# d709-vs1053-synth.net
KiCad netlist of a schematic drawn in EAGLE
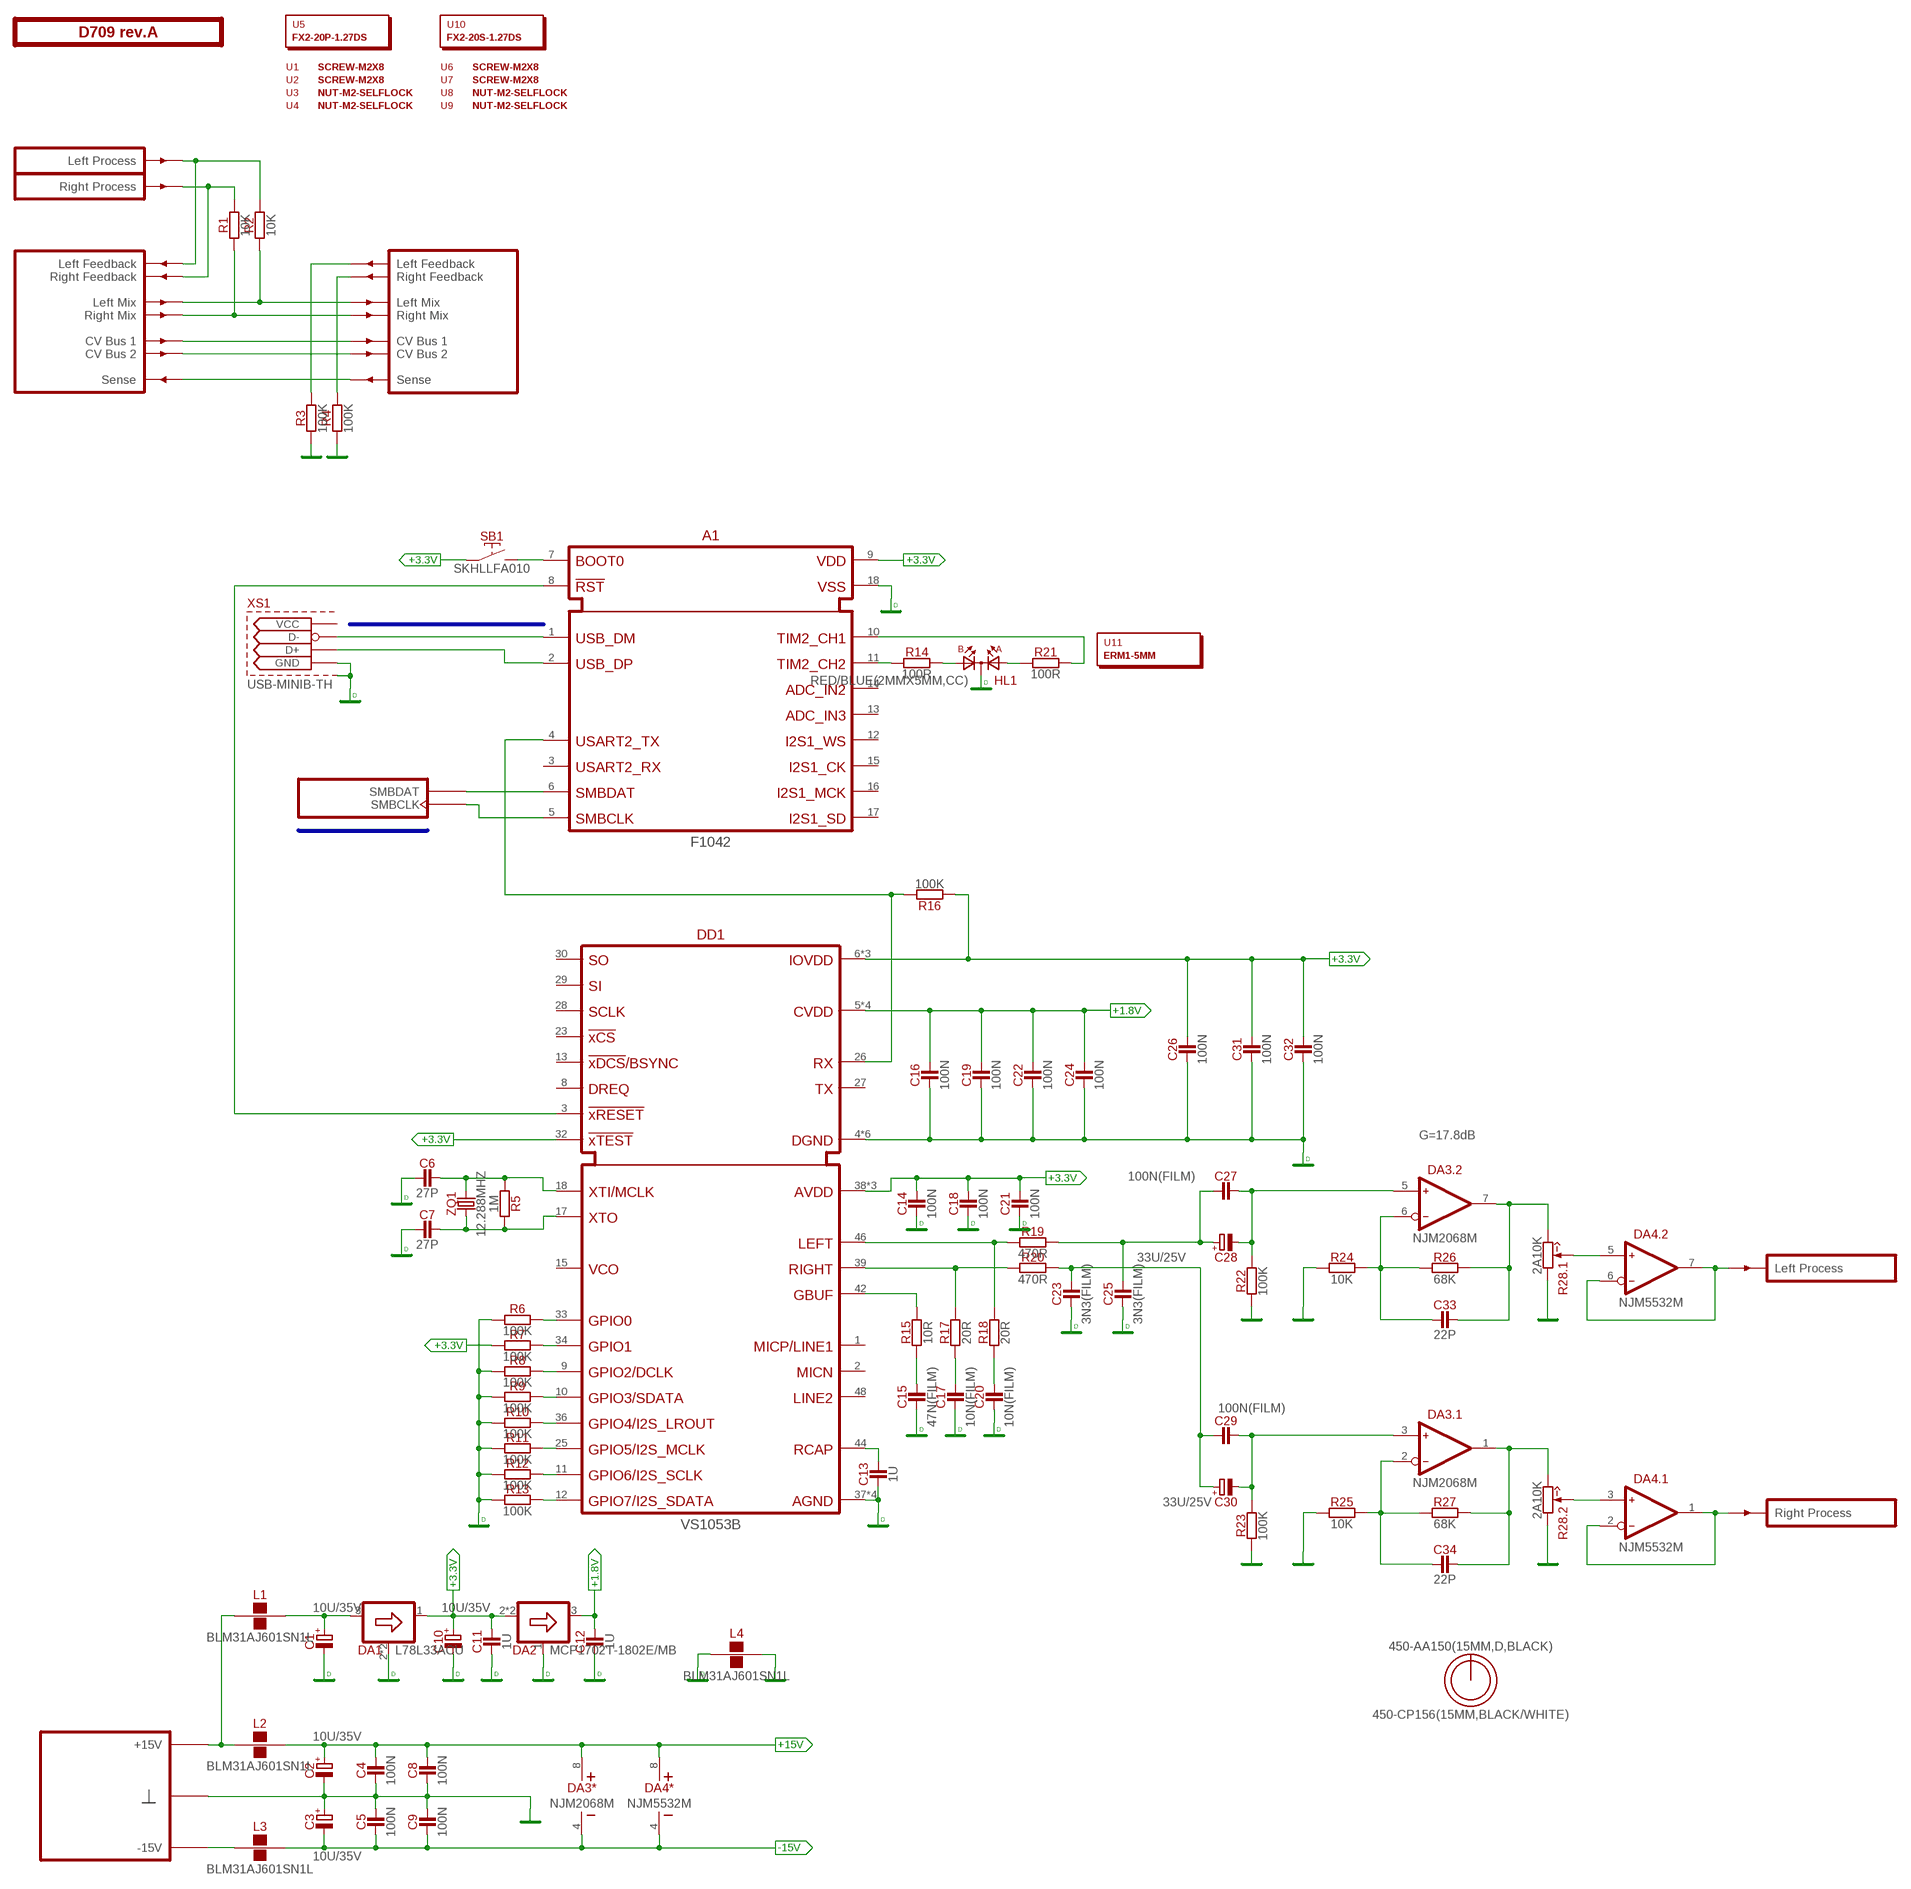
[diagram p0: schematic, sheet 1]

(export (version "E")
  (design (tool "Eeschema 10.0.6"))
  (components
    (comp (ref "A1")
      (value "F1042")
      (footprint "eagle-import:F-DIP18")
      (libsource (lib "eagle-import") (part "F1042"))
    )
    (comp (ref "C1")
      (value "10U/35V")
      (footprint "eagle-import:E2-5")
      (libsource (lib "eagle-import") (part "?10U/35V"))
    )
    (comp (ref "C2")
      (value "10U/35V")
      (footprint "eagle-import:E2-5")
      (libsource (lib "eagle-import") (part "?10U/35V"))
    )
    (comp (ref "C3")
      (value "10U/35V")
      (footprint "eagle-import:E2-5")
      (libsource (lib "eagle-import") (part "?10U/35V"))
    )
    (comp (ref "C4")
      (value "100N")
      (footprint "eagle-import:C-0805")
      (libsource (lib "eagle-import") (part "?100N"))
    )
    (comp (ref "C5")
      (value "100N")
      (footprint "eagle-import:C-0805")
      (libsource (lib "eagle-import") (part "?100N"))
    )
    (comp (ref "C6")
      (value "27P")
      (footprint "eagle-import:C-0805")
      (libsource (lib "eagle-import") (part "?27P"))
    )
    (comp (ref "C7")
      (value "27P")
      (footprint "eagle-import:C-0805")
      (libsource (lib "eagle-import") (part "?27P"))
    )
    (comp (ref "C8")
      (value "100N")
      (footprint "eagle-import:C-0805")
      (libsource (lib "eagle-import") (part "?100N"))
    )
    (comp (ref "C9")
      (value "100N")
      (footprint "eagle-import:C-0805")
      (libsource (lib "eagle-import") (part "?100N"))
    )
    (comp (ref "C10")
      (value "10U/35V")
      (footprint "eagle-import:E2-5")
      (libsource (lib "eagle-import") (part "?10U/35V"))
    )
    (comp (ref "C11")
      (value "1U")
      (footprint "eagle-import:C-0805")
      (libsource (lib "eagle-import") (part "?1U"))
    )
    (comp (ref "C12")
      (value "1U")
      (footprint "eagle-import:C-0805")
      (libsource (lib "eagle-import") (part "?1U"))
    )
    (comp (ref "C13")
      (value "1U")
      (footprint "eagle-import:C-0805")
      (libsource (lib "eagle-import") (part "?1U"))
    )
    (comp (ref "C14")
      (value "100N")
      (footprint "eagle-import:C-0805")
      (libsource (lib "eagle-import") (part "?100N"))
    )
    (comp (ref "C15")
      (value "47N(FILM)")
      (footprint "eagle-import:C050-025X075")
      (libsource (lib "eagle-import") (part "?47N(FILM)"))
    )
    (comp (ref "C16")
      (value "100N")
      (footprint "eagle-import:C-0805")
      (libsource (lib "eagle-import") (part "?100N"))
    )
    (comp (ref "C17")
      (value "10N(FILM)")
      (footprint "eagle-import:C050-025X075")
      (libsource (lib "eagle-import") (part "?10N(FILM)"))
    )
    (comp (ref "C18")
      (value "100N")
      (footprint "eagle-import:C-0805")
      (libsource (lib "eagle-import") (part "?100N"))
    )
    (comp (ref "C19")
      (value "100N")
      (footprint "eagle-import:C-0805")
      (libsource (lib "eagle-import") (part "?100N"))
    )
    (comp (ref "C20")
      (value "10N(FILM)")
      (footprint "eagle-import:C050-025X075")
      (libsource (lib "eagle-import") (part "?10N(FILM)"))
    )
    (comp (ref "C21")
      (value "100N")
      (footprint "eagle-import:C-0805")
      (libsource (lib "eagle-import") (part "?100N"))
    )
    (comp (ref "C22")
      (value "100N")
      (footprint "eagle-import:C-0805")
      (libsource (lib "eagle-import") (part "?100N"))
    )
    (comp (ref "C23")
      (value "3N3(FILM)")
      (footprint "eagle-import:C050-025X075")
      (libsource (lib "eagle-import") (part "?3N3(FILM)"))
    )
    (comp (ref "C24")
      (value "100N")
      (footprint "eagle-import:C-0805")
      (libsource (lib "eagle-import") (part "?100N"))
    )
    (comp (ref "C25")
      (value "3N3(FILM)")
      (footprint "eagle-import:C050-025X075")
      (libsource (lib "eagle-import") (part "?3N3(FILM)"))
    )
    (comp (ref "C26")
      (value "100N")
      (footprint "eagle-import:C-0805")
      (libsource (lib "eagle-import") (part "?100N"))
    )
    (comp (ref "C27")
      (value "100N(FILM)")
      (footprint "eagle-import:C050-025X075")
      (libsource (lib "eagle-import") (part "?100N(FILM)"))
    )
    (comp (ref "C28")
      (value "33U/25V")
      (footprint "eagle-import:E2,5-7")
      (libsource (lib "eagle-import") (part "?33U/25V"))
    )
    (comp (ref "C29")
      (value "100N(FILM)")
      (footprint "eagle-import:C050-025X075")
      (libsource (lib "eagle-import") (part "?100N(FILM)"))
    )
    (comp (ref "C30")
      (value "33U/25V")
      (footprint "eagle-import:E2,5-7")
      (libsource (lib "eagle-import") (part "?33U/25V"))
    )
    (comp (ref "C31")
      (value "100N")
      (footprint "eagle-import:C-0805")
      (libsource (lib "eagle-import") (part "?100N"))
    )
    (comp (ref "C32")
      (value "100N")
      (footprint "eagle-import:C-0805")
      (libsource (lib "eagle-import") (part "?100N"))
    )
    (comp (ref "C33")
      (value "22P")
      (footprint "eagle-import:C-0805")
      (libsource (lib "eagle-import") (part "?22P"))
    )
    (comp (ref "C34")
      (value "22P")
      (footprint "eagle-import:C-0805")
      (libsource (lib "eagle-import") (part "?22P"))
    )
    (comp (ref "DA1")
      (value "L78L33ACU")
      (footprint "eagle-import:SOT89")
      (libsource (lib "eagle-import") (part "?L78L33ACU"))
    )
    (comp (ref "DA2")
      (value "MCP1702T-1802E/MB")
      (footprint "eagle-import:SOT89")
      (libsource (lib "eagle-import") (part "?MCP1702T-1802E/MB"))
    )
    (comp (ref "DA3")
      (value "NJM2068M")
      (footprint "eagle-import:SO-8")
      (libsource (lib "eagle-import") (part "NJM2068M"))
    )
    (comp (ref "DA4")
      (value "NJM5532M")
      (footprint "eagle-import:SO-8")
      (libsource (lib "eagle-import") (part "NJM5532M"))
    )
    (comp (ref "DD1")
      (value "VS1053B")
      (footprint "eagle-import:LQFP48-7X7")
      (libsource (lib "eagle-import") (part "VS1053B"))
    )
    (comp (ref "HL1")
      (value "RED/BLUE(2MMX5MM,CC)")
      (footprint "eagle-import:LED2X5-3PIN")
      (libsource (lib "eagle-import") (part "?(2MMX5MM,CC)RED/BLUE"))
    )
    (comp (ref "L1")
      (value "BLM31AJ601SN1L")
      (footprint "eagle-import:1206")
      (libsource (lib "eagle-import") (part "BLM31AJ601SN1L"))
    )
    (comp (ref "L2")
      (value "BLM31AJ601SN1L")
      (footprint "eagle-import:1206")
      (libsource (lib "eagle-import") (part "BLM31AJ601SN1L"))
    )
    (comp (ref "L3")
      (value "BLM31AJ601SN1L")
      (footprint "eagle-import:1206")
      (libsource (lib "eagle-import") (part "BLM31AJ601SN1L"))
    )
    (comp (ref "L4")
      (value "BLM31AJ601SN1L")
      (footprint "eagle-import:1206")
      (libsource (lib "eagle-import") (part "BLM31AJ601SN1L"))
    )
    (comp (ref "O1")
      (value "450-AA150(15MM,D,BLACK)")
      (footprint "eagle-import:EMPTY")
      (libsource (lib "eagle-import") (part "450-AA?150(15MM,D,BLACK)"))
    )
    (comp (ref "O2")
      (value "450-CP156(15MM,BLACK/WHITE)")
      (footprint "eagle-import:EMPTY")
      (libsource (lib "eagle-import") (part "450-C?P156(15MM,BLACK/WHITE)"))
    )
    (comp (ref "PCB1")
      (value "D709 rev.A")
      (footprint "eagle-import:ST2-BOARD-50")
      (libsource (lib "eagle-import") (part "ST2-BOARD-?50"))
    )
    (comp (ref "R1")
      (value "10K")
      (footprint "eagle-import:R-0805")
      (libsource (lib "eagle-import") (part "?10K"))
    )
    (comp (ref "R2")
      (value "10K")
      (footprint "eagle-import:R-0805")
      (libsource (lib "eagle-import") (part "?10K"))
    )
    (comp (ref "R3")
      (value "100K")
      (footprint "eagle-import:R-0805")
      (libsource (lib "eagle-import") (part "?100K"))
    )
    (comp (ref "R4")
      (value "100K")
      (footprint "eagle-import:R-0805")
      (libsource (lib "eagle-import") (part "?100K"))
    )
    (comp (ref "R5")
      (value "1M")
      (footprint "eagle-import:R-0805")
      (libsource (lib "eagle-import") (part "?1M"))
    )
    (comp (ref "R6")
      (value "100K")
      (footprint "eagle-import:R-0805")
      (libsource (lib "eagle-import") (part "?100K"))
    )
    (comp (ref "R7")
      (value "100K")
      (footprint "eagle-import:R-0805")
      (libsource (lib "eagle-import") (part "?100K"))
    )
    (comp (ref "R8")
      (value "100K")
      (footprint "eagle-import:R-0805")
      (libsource (lib "eagle-import") (part "?100K"))
    )
    (comp (ref "R9")
      (value "100K")
      (footprint "eagle-import:R-0805")
      (libsource (lib "eagle-import") (part "?100K"))
    )
    (comp (ref "R10")
      (value "100K")
      (footprint "eagle-import:R-0805")
      (libsource (lib "eagle-import") (part "?100K"))
    )
    (comp (ref "R11")
      (value "100K")
      (footprint "eagle-import:R-0805")
      (libsource (lib "eagle-import") (part "?100K"))
    )
    (comp (ref "R12")
      (value "100K")
      (footprint "eagle-import:R-0805")
      (libsource (lib "eagle-import") (part "?100K"))
    )
    (comp (ref "R13")
      (value "100K")
      (footprint "eagle-import:R-0805")
      (libsource (lib "eagle-import") (part "?100K"))
    )
    (comp (ref "R14")
      (value "100R")
      (footprint "eagle-import:R-0805")
      (libsource (lib "eagle-import") (part "?100R"))
    )
    (comp (ref "R15")
      (value "10R")
      (footprint "eagle-import:R-0805")
      (libsource (lib "eagle-import") (part "?10R"))
    )
    (comp (ref "R16")
      (value "100K")
      (footprint "eagle-import:R-0805")
      (libsource (lib "eagle-import") (part "?100K"))
    )
    (comp (ref "R17")
      (value "20R")
      (footprint "eagle-import:R-0805")
      (libsource (lib "eagle-import") (part "?20R"))
    )
    (comp (ref "R18")
      (value "20R")
      (footprint "eagle-import:R-0805")
      (libsource (lib "eagle-import") (part "?20R"))
    )
    (comp (ref "R19")
      (value "470R")
      (footprint "eagle-import:R-0805")
      (libsource (lib "eagle-import") (part "?470R"))
    )
    (comp (ref "R20")
      (value "470R")
      (footprint "eagle-import:R-0805")
      (libsource (lib "eagle-import") (part "?470R"))
    )
    (comp (ref "R21")
      (value "100R")
      (footprint "eagle-import:R-0805")
      (libsource (lib "eagle-import") (part "?100R"))
    )
    (comp (ref "R22")
      (value "100K")
      (footprint "eagle-import:R-0805")
      (libsource (lib "eagle-import") (part "?100K"))
    )
    (comp (ref "R23")
      (value "100K")
      (footprint "eagle-import:R-0805")
      (libsource (lib "eagle-import") (part "?100K"))
    )
    (comp (ref "R24")
      (value "10K")
      (footprint "eagle-import:R-0805")
      (libsource (lib "eagle-import") (part "?10K"))
    )
    (comp (ref "R25")
      (value "10K")
      (footprint "eagle-import:R-0805")
      (libsource (lib "eagle-import") (part "?10K"))
    )
    (comp (ref "R26")
      (value "68K")
      (footprint "eagle-import:R-0805")
      (libsource (lib "eagle-import") (part "?68K"))
    )
    (comp (ref "R27")
      (value "68K")
      (footprint "eagle-import:R-0805")
      (libsource (lib "eagle-import") (part "?68K"))
    )
    (comp (ref "R28")
      (value "2A10K")
      (footprint "eagle-import:RV11-DUAL")
      (libsource (lib "eagle-import") (part "2?A10K"))
    )
    (comp (ref "SB1")
      (value "SKHLLFA010")
      (footprint "eagle-import:SKHLLFA010")
      (libsource (lib "eagle-import") (part "SKHLLFA010"))
    )
    (comp (ref "U1")
      (value "SCREW-M2X8")
      (footprint "eagle-import:EMPTY")
      (libsource (lib "eagle-import") (part "?SCREW-M2X8"))
    )
    (comp (ref "U2")
      (value "SCREW-M2X8")
      (footprint "eagle-import:EMPTY")
      (libsource (lib "eagle-import") (part "?SCREW-M2X8"))
    )
    (comp (ref "U3")
      (value "NUT-M2-SELFLOCK")
      (footprint "eagle-import:EMPTY")
      (libsource (lib "eagle-import") (part "?NUT-M2-SELFLOCK"))
    )
    (comp (ref "U4")
      (value "NUT-M2-SELFLOCK")
      (footprint "eagle-import:EMPTY")
      (libsource (lib "eagle-import") (part "?NUT-M2-SELFLOCK"))
    )
    (comp (ref "U5")
      (value "FX2-20P-1.27DS")
      (footprint "eagle-import:EMPTY")
      (libsource (lib "eagle-import") (part "?FX2-20P-1.27DS"))
    )
    (comp (ref "U6")
      (value "SCREW-M2X8")
      (footprint "eagle-import:EMPTY")
      (libsource (lib "eagle-import") (part "?SCREW-M2X8"))
    )
    (comp (ref "U7")
      (value "SCREW-M2X8")
      (footprint "eagle-import:EMPTY")
      (libsource (lib "eagle-import") (part "?SCREW-M2X8"))
    )
    (comp (ref "U8")
      (value "NUT-M2-SELFLOCK")
      (footprint "eagle-import:EMPTY")
      (libsource (lib "eagle-import") (part "?NUT-M2-SELFLOCK"))
    )
    (comp (ref "U9")
      (value "NUT-M2-SELFLOCK")
      (footprint "eagle-import:EMPTY")
      (libsource (lib "eagle-import") (part "?NUT-M2-SELFLOCK"))
    )
    (comp (ref "U10")
      (value "FX2-20S-1.27DS")
      (footprint "eagle-import:EMPTY")
      (libsource (lib "eagle-import") (part "?FX2-20S-1.27DS"))
    )
    (comp (ref "U11")
      (value "ERM1-5MM")
      (footprint "eagle-import:EMPTY")
      (libsource (lib "eagle-import") (part "?ERM1-5MM"))
    )
    (comp (ref "XS1")
      (value "USB-MINIB-TH")
      (footprint "eagle-import:USB-MB-H")
      (libsource (lib "eagle-import") (part "USB-MINIB-TH"))
    )
    (comp (ref "ZQ1")
      (value "12.288MHZ")
      (footprint "eagle-import:3225")
      (libsource (lib "eagle-import") (part "?12.288MHZ"))
    )
  )
  (nets
    (net (code "1") (name "+1.8V") (class "Default")
      (node (ref "C12") (pin "2") (pinfunction "2_2") (pintype "passive"))
      (node (ref "C16") (pin "2") (pinfunction "2_2") (pintype "passive"))
      (node (ref "C19") (pin "2") (pinfunction "2_2") (pintype "passive"))
      (node (ref "C22") (pin "2") (pinfunction "2_2") (pintype "passive"))
      (node (ref "C24") (pin "2") (pinfunction "2_2") (pintype "passive"))
      (node (ref "DA2") (pin "3") (pinfunction "OUT_3") (pintype "power_in"))
      (node (ref "DD1") (pin "24") (pinfunction "CVDD_24") (pintype "input"))
      (node (ref "DD1") (pin "31") (pinfunction "CVDD_31") (pintype "input"))
      (node (ref "DD1") (pin "5") (pinfunction "CVDD_5") (pintype "input"))
      (node (ref "DD1") (pin "7") (pinfunction "CVDD_7") (pintype "input"))
    )
    (net (code "2") (name "+3.3V") (class "Default")
      (node (ref "A1") (pin "9") (pinfunction "VDD_9") (pintype "input"))
      (node (ref "C10") (pin "+") (pinfunction "+_+") (pintype "passive"))
      (node (ref "C11") (pin "2") (pinfunction "2_2") (pintype "passive"))
      (node (ref "C14") (pin "2") (pinfunction "2_2") (pintype "passive"))
      (node (ref "C18") (pin "2") (pinfunction "2_2") (pintype "passive"))
      (node (ref "C21") (pin "2") (pinfunction "2_2") (pintype "passive"))
      (node (ref "C26") (pin "2") (pinfunction "2_2") (pintype "passive"))
      (node (ref "C31") (pin "2") (pinfunction "2_2") (pintype "passive"))
      (node (ref "C32") (pin "2") (pinfunction "2_2") (pintype "passive"))
      (node (ref "DA1") (pin "1") (pinfunction "OUT_1") (pintype "power_in"))
      (node (ref "DA2") (pin "2") (pinfunction "IN_2") (pintype "power_in"))
      (node (ref "DA2") (pin "2@1") (pinfunction "IN_2@1") (pintype "power_in"))
      (node (ref "DD1") (pin "14") (pinfunction "IOVDD_14") (pintype "input"))
      (node (ref "DD1") (pin "19") (pinfunction "IOVDD_19") (pintype "input"))
      (node (ref "DD1") (pin "32") (pinfunction "~{XTEST}_32") (pintype "input"))
      (node (ref "DD1") (pin "38") (pinfunction "AVDD_38") (pintype "input"))
      (node (ref "DD1") (pin "43") (pinfunction "AVDD_43") (pintype "input"))
      (node (ref "DD1") (pin "45") (pinfunction "AVDD_45") (pintype "input"))
      (node (ref "DD1") (pin "6") (pinfunction "IOVDD_6") (pintype "input"))
      (node (ref "R16") (pin "1") (pinfunction "1_1") (pintype "passive"))
      (node (ref "R7") (pin "1") (pinfunction "1_1") (pintype "passive"))
      (node (ref "SB1") (pin "1") (pinfunction "1_1") (pintype "passive"))
    )
    (net (code "3") (name "+15V") (class "Default")
      (node (ref "C2") (pin "+") (pinfunction "+_+") (pintype "passive"))
      (node (ref "C4") (pin "2") (pinfunction "2_2") (pintype "passive"))
      (node (ref "C8") (pin "2") (pinfunction "2_2") (pintype "passive"))
      (node (ref "DA3") (pin "8") (pinfunction "V+_8") (pintype "power_in"))
      (node (ref "DA4") (pin "8") (pinfunction "V+_8") (pintype "power_in"))
      (node (ref "L2") (pin "2") (pinfunction "2_2") (pintype "passive"))
    )
    (net (code "4") (name "-15V") (class "Default")
      (node (ref "C3") (pin "-") (pinfunction "-_-") (pintype "passive"))
      (node (ref "C5") (pin "1") (pinfunction "1_1") (pintype "passive"))
      (node (ref "C9") (pin "1") (pinfunction "1_1") (pintype "passive"))
      (node (ref "DA3") (pin "4") (pinfunction "V-_4") (pintype "power_in"))
      (node (ref "DA4") (pin "4") (pinfunction "V-_4") (pintype "power_in"))
      (node (ref "L3") (pin "2") (pinfunction "2_2") (pintype "passive"))
    )
    (net (code "5") (name "DGND") (class "Default")
      (node (ref "A1") (pin "18") (pinfunction "VSS_18") (pintype "input"))
      (node (ref "C1") (pin "-") (pinfunction "-_-") (pintype "passive"))
      (node (ref "C10") (pin "-") (pinfunction "-_-") (pintype "passive"))
      (node (ref "C11") (pin "1") (pinfunction "1_1") (pintype "passive"))
      (node (ref "C12") (pin "1") (pinfunction "1_1") (pintype "passive"))
      (node (ref "C13") (pin "1") (pinfunction "1_1") (pintype "passive"))
      (node (ref "C14") (pin "1") (pinfunction "1_1") (pintype "passive"))
      (node (ref "C15") (pin "1") (pinfunction "1_1") (pintype "passive"))
      (node (ref "C16") (pin "1") (pinfunction "1_1") (pintype "passive"))
      (node (ref "C17") (pin "1") (pinfunction "1_1") (pintype "passive"))
      (node (ref "C18") (pin "1") (pinfunction "1_1") (pintype "passive"))
      (node (ref "C19") (pin "1") (pinfunction "1_1") (pintype "passive"))
      (node (ref "C20") (pin "1") (pinfunction "1_1") (pintype "passive"))
      (node (ref "C21") (pin "1") (pinfunction "1_1") (pintype "passive"))
      (node (ref "C22") (pin "1") (pinfunction "1_1") (pintype "passive"))
      (node (ref "C23") (pin "1") (pinfunction "1_1") (pintype "passive"))
      (node (ref "C24") (pin "1") (pinfunction "1_1") (pintype "passive"))
      (node (ref "C25") (pin "1") (pinfunction "1_1") (pintype "passive"))
      (node (ref "C26") (pin "1") (pinfunction "1_1") (pintype "passive"))
      (node (ref "C31") (pin "1") (pinfunction "1_1") (pintype "passive"))
      (node (ref "C32") (pin "1") (pinfunction "1_1") (pintype "passive"))
      (node (ref "C6") (pin "1") (pinfunction "1_1") (pintype "passive"))
      (node (ref "C7") (pin "1") (pinfunction "1_1") (pintype "passive"))
      (node (ref "DA1") (pin "2") (pinfunction "GND_2") (pintype "power_in"))
      (node (ref "DA1") (pin "2@1") (pinfunction "GND_2@1") (pintype "power_in"))
      (node (ref "DA2") (pin "1") (pinfunction "GND_1") (pintype "power_in"))
      (node (ref "DD1") (pin "16") (pinfunction "DGND_16") (pintype "input"))
      (node (ref "DD1") (pin "20") (pinfunction "DGND_20") (pintype "input"))
      (node (ref "DD1") (pin "21") (pinfunction "DGND_21") (pintype "input"))
      (node (ref "DD1") (pin "22") (pinfunction "DGND_22") (pintype "input"))
      (node (ref "DD1") (pin "35") (pinfunction "DGND_35") (pintype "input"))
      (node (ref "DD1") (pin "37") (pinfunction "AGND_37") (pintype "input"))
      (node (ref "DD1") (pin "4") (pinfunction "DGND_4") (pintype "input"))
      (node (ref "DD1") (pin "40") (pinfunction "AGND_40") (pintype "input"))
      (node (ref "DD1") (pin "41") (pinfunction "AGND_41") (pintype "input"))
      (node (ref "DD1") (pin "47") (pinfunction "AGND_47") (pintype "input"))
      (node (ref "HL1") (pin "K") (pinfunction "K_K") (pintype "passive"))
      (node (ref "L4") (pin "1") (pinfunction "1_1") (pintype "passive"))
      (node (ref "R10") (pin "1") (pinfunction "1_1") (pintype "passive"))
      (node (ref "R11") (pin "1") (pinfunction "1_1") (pintype "passive"))
      (node (ref "R12") (pin "1") (pinfunction "1_1") (pintype "passive"))
      (node (ref "R13") (pin "1") (pinfunction "1_1") (pintype "passive"))
      (node (ref "R6") (pin "1") (pinfunction "1_1") (pintype "passive"))
      (node (ref "R8") (pin "1") (pinfunction "1_1") (pintype "passive"))
      (node (ref "R9") (pin "1") (pinfunction "1_1") (pintype "passive"))
      (node (ref "XS1") (pin "GND") (pinfunction "GND_GND") (pintype "passive"))
      (node (ref "XS1") (pin "P$1") (pinfunction "S1_P$1") (pintype "passive"))
      (node (ref "XS1") (pin "P$2") (pinfunction "S1_P$2") (pintype "passive"))
      (node (ref "XS1") (pin "P$6") (pinfunction "S1_P$6") (pintype "passive"))
      (node (ref "XS1") (pin "P$7") (pinfunction "S1_P$7") (pintype "passive"))
    )
    (net (code "6") (name "GND") (class "Default")
      (node (ref "C2") (pin "-") (pinfunction "-_-") (pintype "passive"))
      (node (ref "C3") (pin "+") (pinfunction "+_+") (pintype "passive"))
      (node (ref "C4") (pin "1") (pinfunction "1_1") (pintype "passive"))
      (node (ref "C5") (pin "2") (pinfunction "2_2") (pintype "passive"))
      (node (ref "C8") (pin "1") (pinfunction "1_1") (pintype "passive"))
      (node (ref "C9") (pin "2") (pinfunction "2_2") (pintype "passive"))
      (node (ref "L4") (pin "2") (pinfunction "2_2") (pintype "passive"))
      (node (ref "PCB1") (pin "B4") (pinfunction "GND_B4") (pintype "bidirectional"))
      (node (ref "PCB1") (pin "B4'") (pinfunction "GND_B4'") (pintype "bidirectional"))
      (node (ref "PCB1") (pin "B5") (pinfunction "GND_B5") (pintype "bidirectional"))
      (node (ref "PCB1") (pin "B5'") (pinfunction "GND_B5'") (pintype "bidirectional"))
      (node (ref "PCB1") (pin "B6") (pinfunction "GND_B6") (pintype "bidirectional"))
      (node (ref "PCB1") (pin "B6'") (pinfunction "GND_B6'") (pintype "bidirectional"))
      (node (ref "PCB1") (pin "B7") (pinfunction "GND_B7") (pintype "bidirectional"))
      (node (ref "PCB1") (pin "B7'") (pinfunction "GND_B7'") (pintype "bidirectional"))
      (node (ref "PCB1") (pin "B8") (pinfunction "GND_B8") (pintype "bidirectional"))
      (node (ref "PCB1") (pin "B8'") (pinfunction "GND_B8'") (pintype "bidirectional"))
      (node (ref "R22") (pin "1") (pinfunction "1_1") (pintype "passive"))
      (node (ref "R23") (pin "1") (pinfunction "1_1") (pintype "passive"))
      (node (ref "R24") (pin "1") (pinfunction "1_1") (pintype "passive"))
      (node (ref "R25") (pin "1") (pinfunction "1_1") (pintype "passive"))
      (node (ref "R28") (pin "1") (pinfunction "CCW_1") (pintype "passive"))
      (node (ref "R28") (pin "1'") (pinfunction "CCW_1'") (pintype "passive"))
      (node (ref "R3") (pin "1") (pinfunction "1_1") (pintype "passive"))
      (node (ref "R4") (pin "1") (pinfunction "1_1") (pintype "passive"))
    )
    (net (code "7") (name "Net-(A1-BOOT0)") (class "Default")
      (node (ref "A1") (pin "7") (pinfunction "BOOT0_7") (pintype "input"))
      (node (ref "SB1") (pin "2") (pinfunction "2_2") (pintype "passive"))
    )
    (net (code "8") (name "Net-(A1-SBMDAT)") (class "Default")
      (node (ref "A1") (pin "6") (pinfunction "SBMDAT_6") (pintype "input"))
      (node (ref "PCB1") (pin "ASMBDAT") (pinfunction "SMBDAT_ASMBDAT") (pintype "bidirectional"))
      (node (ref "PCB1") (pin "ASMBDAT'") (pinfunction "SMBDAT_ASMBDAT'") (pintype "bidirectional"))
    )
    (net (code "9") (name "Net-(A1-SMBCLK)") (class "Default")
      (node (ref "A1") (pin "5") (pinfunction "SMBCLK_5") (pintype "input"))
      (node (ref "PCB1") (pin "ASMBCLK") (pinfunction "SMBCLK_ASMBCLK") (pintype "bidirectional"))
      (node (ref "PCB1") (pin "ASMBCLK'") (pinfunction "SMBCLK_ASMBCLK'") (pintype "bidirectional"))
    )
    (net (code "10") (name "Net-(A1-TIM2_CH1)") (class "Default")
      (node (ref "A1") (pin "10") (pinfunction "TIM2_CH1_10") (pintype "input"))
      (node (ref "R21") (pin "2") (pinfunction "2_2") (pintype "passive"))
    )
    (net (code "11") (name "Net-(A1-TIM2_CH2)") (class "Default")
      (node (ref "A1") (pin "11") (pinfunction "TIM2_CH2_11") (pintype "input"))
      (node (ref "R14") (pin "1") (pinfunction "1_1") (pintype "passive"))
    )
    (net (code "12") (name "Net-(A1-USART2_TX)") (class "Default")
      (node (ref "A1") (pin "4") (pinfunction "USART2_TX_4") (pintype "input"))
      (node (ref "DD1") (pin "26") (pinfunction "RX_26") (pintype "input"))
      (node (ref "R16") (pin "2") (pinfunction "2_2") (pintype "passive"))
    )
    (net (code "13") (name "Net-(A1-USB_DM)") (class "Default")
      (node (ref "A1") (pin "1") (pinfunction "USB_DM_1") (pintype "input"))
      (node (ref "XS1") (pin "D-") (pinfunction "D-_D-") (pintype "bidirectional"))
    )
    (net (code "14") (name "Net-(A1-USB_DP)") (class "Default")
      (node (ref "A1") (pin "2") (pinfunction "USB_DP_2") (pintype "input"))
      (node (ref "XS1") (pin "D+") (pinfunction "D+_D+") (pintype "bidirectional"))
    )
    (net (code "15") (name "Net-(A1-~{RST})") (class "Default")
      (node (ref "A1") (pin "8") (pinfunction "~{RST}_8") (pintype "input"))
      (node (ref "DD1") (pin "3") (pinfunction "~{XRESET}_3") (pintype "input"))
    )
    (net (code "16") (name "Net-(C15-Pad2)") (class "Default")
      (node (ref "C15") (pin "2") (pinfunction "2_2") (pintype "passive"))
      (node (ref "R15") (pin "1") (pinfunction "1_1") (pintype "passive"))
    )
    (net (code "17") (name "Net-(C17-Pad2)") (class "Default")
      (node (ref "C17") (pin "2") (pinfunction "2_2") (pintype "passive"))
      (node (ref "R17") (pin "1") (pinfunction "1_1") (pintype "passive"))
    )
    (net (code "18") (name "Net-(C20-Pad2)") (class "Default")
      (node (ref "C20") (pin "2") (pinfunction "2_2") (pintype "passive"))
      (node (ref "R18") (pin "1") (pinfunction "1_1") (pintype "passive"))
    )
    (net (code "19") (name "Net-(C23-Pad2)") (class "Default")
      (node (ref "C23") (pin "2") (pinfunction "2_2") (pintype "passive"))
      (node (ref "C29") (pin "1") (pinfunction "1_1") (pintype "passive"))
      (node (ref "C30") (pin "+") (pinfunction "+_+") (pintype "passive"))
      (node (ref "R20") (pin "2") (pinfunction "2_2") (pintype "passive"))
    )
    (net (code "20") (name "Net-(C25-Pad2)") (class "Default")
      (node (ref "C25") (pin "2") (pinfunction "2_2") (pintype "passive"))
      (node (ref "C27") (pin "1") (pinfunction "1_1") (pintype "passive"))
      (node (ref "C28") (pin "+") (pinfunction "+_+") (pintype "passive"))
      (node (ref "R19") (pin "2") (pinfunction "2_2") (pintype "passive"))
    )
    (net (code "21") (name "Net-(DA1-IN)") (class "Default")
      (node (ref "C1") (pin "+") (pinfunction "+_+") (pintype "passive"))
      (node (ref "DA1") (pin "3") (pinfunction "IN_3") (pintype "power_in"))
      (node (ref "L1") (pin "2") (pinfunction "2_2") (pintype "passive"))
    )
    (net (code "22") (name "Net-(DA3B-IN+)") (class "Default")
      (node (ref "C29") (pin "2") (pinfunction "2_2") (pintype "passive"))
      (node (ref "C30") (pin "-") (pinfunction "-_-") (pintype "passive"))
      (node (ref "DA3") (pin "3") (pinfunction "IN+_3") (pintype "input"))
      (node (ref "R23") (pin "2") (pinfunction "2_2") (pintype "passive"))
    )
    (net (code "23") (name "Net-(DA3B-IN-)") (class "Default")
      (node (ref "C34") (pin "1") (pinfunction "1_1") (pintype "passive"))
      (node (ref "DA3") (pin "2") (pinfunction "IN-_2") (pintype "input"))
      (node (ref "R25") (pin "2") (pinfunction "2_2") (pintype "passive"))
      (node (ref "R27") (pin "1") (pinfunction "1_1") (pintype "passive"))
    )
    (net (code "24") (name "Net-(DA3B-OUT)") (class "Default")
      (node (ref "C34") (pin "2") (pinfunction "2_2") (pintype "passive"))
      (node (ref "DA3") (pin "1") (pinfunction "OUT_1") (pintype "output"))
      (node (ref "R27") (pin "2") (pinfunction "2_2") (pintype "passive"))
      (node (ref "R28") (pin "3'") (pinfunction "CW_3'") (pintype "passive"))
    )
    (net (code "25") (name "Net-(DA3C-IN+)") (class "Default")
      (node (ref "C27") (pin "2") (pinfunction "2_2") (pintype "passive"))
      (node (ref "C28") (pin "-") (pinfunction "-_-") (pintype "passive"))
      (node (ref "DA3") (pin "5") (pinfunction "IN+_5") (pintype "input"))
      (node (ref "R22") (pin "2") (pinfunction "2_2") (pintype "passive"))
    )
    (net (code "26") (name "Net-(DA3C-IN-)") (class "Default")
      (node (ref "C33") (pin "1") (pinfunction "1_1") (pintype "passive"))
      (node (ref "DA3") (pin "6") (pinfunction "IN-_6") (pintype "input"))
      (node (ref "R24") (pin "2") (pinfunction "2_2") (pintype "passive"))
      (node (ref "R26") (pin "1") (pinfunction "1_1") (pintype "passive"))
    )
    (net (code "27") (name "Net-(DA3C-OUT)") (class "Default")
      (node (ref "C33") (pin "2") (pinfunction "2_2") (pintype "passive"))
      (node (ref "DA3") (pin "7") (pinfunction "OUT_7") (pintype "output"))
      (node (ref "R26") (pin "2") (pinfunction "2_2") (pintype "passive"))
      (node (ref "R28") (pin "3") (pinfunction "CW_3") (pintype "passive"))
    )
    (net (code "28") (name "Net-(DA4B-IN+)") (class "Default")
      (node (ref "DA4") (pin "3") (pinfunction "IN+_3") (pintype "input"))
      (node (ref "R28") (pin "2'") (pinfunction "W_2'") (pintype "passive"))
    )
    (net (code "29") (name "Net-(DA4B-IN-)") (class "Default")
      (node (ref "DA4") (pin "1") (pinfunction "OUT_1") (pintype "output"))
      (node (ref "DA4") (pin "2") (pinfunction "IN-_2") (pintype "input"))
      (node (ref "PCB1") (pin "BOUTR'") (pinfunction "OUTR_BOUTR'") (pintype "bidirectional"))
    )
    (net (code "30") (name "Net-(DA4C-IN+)") (class "Default")
      (node (ref "DA4") (pin "5") (pinfunction "IN+_5") (pintype "input"))
      (node (ref "R28") (pin "2") (pinfunction "W_2") (pintype "passive"))
    )
    (net (code "31") (name "Net-(DA4C-IN-)") (class "Default")
      (node (ref "DA4") (pin "6") (pinfunction "IN-_6") (pintype "input"))
      (node (ref "DA4") (pin "7") (pinfunction "OUT_7") (pintype "output"))
      (node (ref "PCB1") (pin "BOUTL'") (pinfunction "OUTL_BOUTL'") (pintype "bidirectional"))
    )
    (net (code "32") (name "Net-(DD1-GBUF)") (class "Default")
      (node (ref "DD1") (pin "42") (pinfunction "GBUF_42") (pintype "input"))
      (node (ref "R15") (pin "2") (pinfunction "2_2") (pintype "passive"))
    )
    (net (code "33") (name "Net-(DD1-GPIO0)") (class "Default")
      (node (ref "DD1") (pin "33") (pinfunction "GPIO0_33") (pintype "input"))
      (node (ref "R6") (pin "2") (pinfunction "2_2") (pintype "passive"))
    )
    (net (code "34") (name "Net-(DD1-GPIO1)") (class "Default")
      (node (ref "DD1") (pin "34") (pinfunction "GPIO1_34") (pintype "input"))
      (node (ref "R7") (pin "2") (pinfunction "2_2") (pintype "passive"))
    )
    (net (code "35") (name "Net-(DD1-GPIO2{slash}DCLK)") (class "Default")
      (node (ref "DD1") (pin "9") (pinfunction "GPIO2/DCLK_9") (pintype "input"))
      (node (ref "R8") (pin "2") (pinfunction "2_2") (pintype "passive"))
    )
    (net (code "36") (name "Net-(DD1-GPIO3{slash}SDATA)") (class "Default")
      (node (ref "DD1") (pin "10") (pinfunction "GPIO3/SDATA_10") (pintype "input"))
      (node (ref "R9") (pin "2") (pinfunction "2_2") (pintype "passive"))
    )
    (net (code "37") (name "Net-(DD1-GPIO4{slash}I2S_LROUT)") (class "Default")
      (node (ref "DD1") (pin "36") (pinfunction "GPIO4/I2S_LROUT_36") (pintype "input"))
      (node (ref "R10") (pin "2") (pinfunction "2_2") (pintype "passive"))
    )
    (net (code "38") (name "Net-(DD1-GPIO5{slash}I2S_MCLK)") (class "Default")
      (node (ref "DD1") (pin "25") (pinfunction "GPIO5/I2S_MCLK_25") (pintype "input"))
      (node (ref "R11") (pin "2") (pinfunction "2_2") (pintype "passive"))
    )
    (net (code "39") (name "Net-(DD1-GPIO6{slash}I2S_SCLK)") (class "Default")
      (node (ref "DD1") (pin "11") (pinfunction "GPIO6/I2S_SCLK_11") (pintype "input"))
      (node (ref "R12") (pin "2") (pinfunction "2_2") (pintype "passive"))
    )
    (net (code "40") (name "Net-(DD1-GPIO7{slash}I2S_SDATA)") (class "Default")
      (node (ref "DD1") (pin "12") (pinfunction "GPIO7/I2S_SDATA_12") (pintype "input"))
      (node (ref "R13") (pin "2") (pinfunction "2_2") (pintype "passive"))
    )
    (net (code "41") (name "Net-(DD1-LEFT)") (class "Default")
      (node (ref "DD1") (pin "46") (pinfunction "LEFT_46") (pintype "input"))
      (node (ref "R18") (pin "2") (pinfunction "2_2") (pintype "passive"))
      (node (ref "R19") (pin "1") (pinfunction "1_1") (pintype "passive"))
    )
    (net (code "42") (name "Net-(DD1-RCAP)") (class "Default")
      (node (ref "C13") (pin "2") (pinfunction "2_2") (pintype "passive"))
      (node (ref "DD1") (pin "44") (pinfunction "RCAP_44") (pintype "input"))
    )
    (net (code "43") (name "Net-(DD1-RIGHT)") (class "Default")
      (node (ref "DD1") (pin "39") (pinfunction "RIGHT_39") (pintype "input"))
      (node (ref "R17") (pin "2") (pinfunction "2_2") (pintype "passive"))
      (node (ref "R20") (pin "1") (pinfunction "1_1") (pintype "passive"))
    )
    (net (code "44") (name "Net-(DD1-XTI{slash}MCLK)") (class "Default")
      (node (ref "C6") (pin "2") (pinfunction "2_2") (pintype "passive"))
      (node (ref "DD1") (pin "18") (pinfunction "XTI/MCLK_18") (pintype "input"))
      (node (ref "R5") (pin "1") (pinfunction "1_1") (pintype "passive"))
      (node (ref "ZQ1") (pin "3") (pinfunction "2_3") (pintype "passive"))
    )
    (net (code "45") (name "Net-(DD1-XTO)") (class "Default")
      (node (ref "C7") (pin "2") (pinfunction "2_2") (pintype "passive"))
      (node (ref "DD1") (pin "17") (pinfunction "XTO_17") (pintype "input"))
      (node (ref "R5") (pin "2") (pinfunction "2_2") (pintype "passive"))
      (node (ref "ZQ1") (pin "1") (pinfunction "1_1") (pintype "passive"))
    )
    (net (code "46") (name "Net-(HL1-PadA1)") (class "Default")
      (node (ref "HL1") (pin "A1") (pinfunction "A1_A1") (pintype "passive"))
      (node (ref "R21") (pin "1") (pinfunction "1_1") (pintype "passive"))
    )
    (net (code "47") (name "Net-(HL1-PadA2)") (class "Default")
      (node (ref "HL1") (pin "A2") (pinfunction "A2_A2") (pintype "passive"))
      (node (ref "R14") (pin "2") (pinfunction "2_2") (pintype "passive"))
    )
    (net (code "48") (name "Net-(L1-Pad1)") (class "Default")
      (node (ref "L1") (pin "1") (pinfunction "1_1") (pintype "passive"))
      (node (ref "L2") (pin "1") (pinfunction "1_1") (pintype "passive"))
      (node (ref "PCB1") (pin "A+15") (pinfunction "P+15V_A+15") (pintype "bidirectional"))
      (node (ref "PCB1") (pin "A+15'") (pinfunction "P+15V_A+15'") (pintype "bidirectional"))
      (node (ref "PCB1") (pin "B+15") (pinfunction "P+15V_B+15") (pintype "bidirectional"))
      (node (ref "PCB1") (pin "B+15'") (pinfunction "P+15V_B+15'") (pintype "bidirectional"))
    )
    (net (code "49") (name "Net-(L3-Pad1)") (class "Default")
      (node (ref "L3") (pin "1") (pinfunction "1_1") (pintype "passive"))
      (node (ref "PCB1") (pin "A-15") (pinfunction "P-15V_A-15") (pintype "bidirectional"))
      (node (ref "PCB1") (pin "A-15'") (pinfunction "P-15V_A-15'") (pintype "bidirectional"))
      (node (ref "PCB1") (pin "B-15") (pinfunction "P-15V_B-15") (pintype "bidirectional"))
      (node (ref "PCB1") (pin "B-15'") (pinfunction "P-15V_B-15'") (pintype "bidirectional"))
    )
    (net (code "50") (name "Net-(PCB1B-INL)") (class "Default")
      (node (ref "PCB1") (pin "ALFBK") (pinfunction "LFBK_ALFBK") (pintype "bidirectional"))
      (node (ref "PCB1") (pin "BINL") (pinfunction "INL_BINL") (pintype "bidirectional"))
      (node (ref "R2") (pin "2") (pinfunction "2_2") (pintype "passive"))
    )
    (net (code "51") (name "Net-(PCB1C-INR)") (class "Default")
      (node (ref "PCB1") (pin "ARFBK") (pinfunction "RFBK_ARFBK") (pintype "bidirectional"))
      (node (ref "PCB1") (pin "BINR") (pinfunction "INR_BINR") (pintype "bidirectional"))
      (node (ref "R1") (pin "2") (pinfunction "2_2") (pintype "passive"))
    )
    (net (code "52") (name "Net-(PCB1F-CV1)") (class "Default")
      (node (ref "PCB1") (pin "ACV1") (pinfunction "CV1_ACV1") (pintype "bidirectional"))
      (node (ref "PCB1") (pin "ACV1'") (pinfunction "CV1'_ACV1'") (pintype "bidirectional"))
    )
    (net (code "53") (name "Net-(PCB1F-CV2)") (class "Default")
      (node (ref "PCB1") (pin "ACV2") (pinfunction "CV2_ACV2") (pintype "bidirectional"))
      (node (ref "PCB1") (pin "ACV2'") (pinfunction "CV2'_ACV2'") (pintype "bidirectional"))
    )
    (net (code "54") (name "Net-(PCB1F-LMIX)") (class "Default")
      (node (ref "PCB1") (pin "ALMIX") (pinfunction "LMIX_ALMIX") (pintype "bidirectional"))
      (node (ref "PCB1") (pin "ALMIX'") (pinfunction "LMIX'_ALMIX'") (pintype "bidirectional"))
      (node (ref "R2") (pin "1") (pinfunction "1_1") (pintype "passive"))
    )
    (net (code "55") (name "Net-(PCB1F-RMIX)") (class "Default")
      (node (ref "PCB1") (pin "ARMIX") (pinfunction "RMIX_ARMIX") (pintype "bidirectional"))
      (node (ref "PCB1") (pin "ARMIX'") (pinfunction "RMIX'_ARMIX'") (pintype "bidirectional"))
      (node (ref "R1") (pin "1") (pinfunction "1_1") (pintype "passive"))
    )
    (net (code "56") (name "Net-(PCB1F-SENSE)") (class "Default")
      (node (ref "PCB1") (pin "BSENSE") (pinfunction "SENSE_BSENSE") (pintype "bidirectional"))
      (node (ref "PCB1") (pin "BSENSE'") (pinfunction "SENSE'_BSENSE'") (pintype "bidirectional"))
    )
    (net (code "57") (name "Net-(PCB1G-LFBK')") (class "Default")
      (node (ref "PCB1") (pin "ALFBK'") (pinfunction "LFBK'_ALFBK'") (pintype "bidirectional"))
      (node (ref "R3") (pin "2") (pinfunction "2_2") (pintype "passive"))
    )
    (net (code "58") (name "Net-(PCB1G-RFBK')") (class "Default")
      (node (ref "PCB1") (pin "ARFBK'") (pinfunction "RFBK'_ARFBK'") (pintype "bidirectional"))
      (node (ref "R4") (pin "2") (pinfunction "2_2") (pintype "passive"))
    )
    (net (code "59") (name "unconnected-(A1-ADC_IN2-Pad14)") (class "Default")
      (node (ref "A1") (pin "14") (pinfunction "ADC_IN2_14") (pintype "input"))
    )
    (net (code "60") (name "unconnected-(A1-ADC_IN3-Pad13)") (class "Default")
      (node (ref "A1") (pin "13") (pinfunction "ADC_IN3_13") (pintype "input"))
    )
    (net (code "61") (name "unconnected-(A1-I2S1_CK-Pad15)") (class "Default")
      (node (ref "A1") (pin "15") (pinfunction "I2S1_CK_15") (pintype "input"))
    )
    (net (code "62") (name "unconnected-(A1-I2S1_MCK-Pad16)") (class "Default")
      (node (ref "A1") (pin "16") (pinfunction "I2S1_MCK_16") (pintype "input"))
    )
    (net (code "63") (name "unconnected-(A1-I2S1_SD-Pad17)") (class "Default")
      (node (ref "A1") (pin "17") (pinfunction "I2S1_SD_17") (pintype "input"))
    )
    (net (code "64") (name "unconnected-(A1-I2S1_WS-Pad12)") (class "Default")
      (node (ref "A1") (pin "12") (pinfunction "I2S1_WS_12") (pintype "input"))
    )
    (net (code "65") (name "unconnected-(A1-USART2_RX-Pad3)") (class "Default")
      (node (ref "A1") (pin "3") (pinfunction "USART2_RX_3") (pintype "input"))
    )
    (net (code "66") (name "unconnected-(DD1-DREQ-Pad8)") (class "Default")
      (node (ref "DD1") (pin "8") (pinfunction "DREQ_8") (pintype "input"))
    )
    (net (code "67") (name "unconnected-(DD1-LINE2-Pad48)") (class "Default")
      (node (ref "DD1") (pin "48") (pinfunction "LINE2_48") (pintype "input"))
    )
    (net (code "68") (name "unconnected-(DD1-MICN-Pad2)") (class "Default")
      (node (ref "DD1") (pin "2") (pinfunction "MICN_2") (pintype "input"))
    )
    (net (code "69") (name "unconnected-(DD1-MICP{slash}LINE1-Pad1)") (class "Default")
      (node (ref "DD1") (pin "1") (pinfunction "MICP/LINE1_1") (pintype "input"))
    )
    (net (code "70") (name "unconnected-(DD1-SCLK-Pad28)") (class "Default")
      (node (ref "DD1") (pin "28") (pinfunction "SCLK_28") (pintype "input"))
    )
    (net (code "71") (name "unconnected-(DD1-SI-Pad29)") (class "Default")
      (node (ref "DD1") (pin "29") (pinfunction "SI_29") (pintype "input"))
    )
    (net (code "72") (name "unconnected-(DD1-SO-Pad30)") (class "Default")
      (node (ref "DD1") (pin "30") (pinfunction "SO_30") (pintype "input"))
    )
    (net (code "73") (name "unconnected-(DD1-TX-Pad27)") (class "Default")
      (node (ref "DD1") (pin "27") (pinfunction "TX_27") (pintype "input"))
    )
    (net (code "74") (name "unconnected-(DD1-VCO-Pad15)") (class "Default")
      (node (ref "DD1") (pin "15") (pinfunction "VCO_15") (pintype "input"))
    )
    (net (code "75") (name "unconnected-(DD1-~{XCS}-Pad23)") (class "Default")
      (node (ref "DD1") (pin "23") (pinfunction "~{XCS}_23") (pintype "input"))
    )
    (net (code "76") (name "unconnected-(DD1-~{XDCS{slash}BSYNC}-Pad13)") (class "Default")
      (node (ref "DD1") (pin "13") (pinfunction "~{XDCS/BSYNC}_13") (pintype "input"))
    )
    (net (code "77") (name "unconnected-(XS1-VCC-PadVBUS)") (class "Default")
      (node (ref "XS1") (pin "VBUS") (pinfunction "VCC_VBUS") (pintype "passive"))
    )
  )
)
